# LCD-Shield_V2.net
KiCad netlist of a schematic drawn in EAGLE
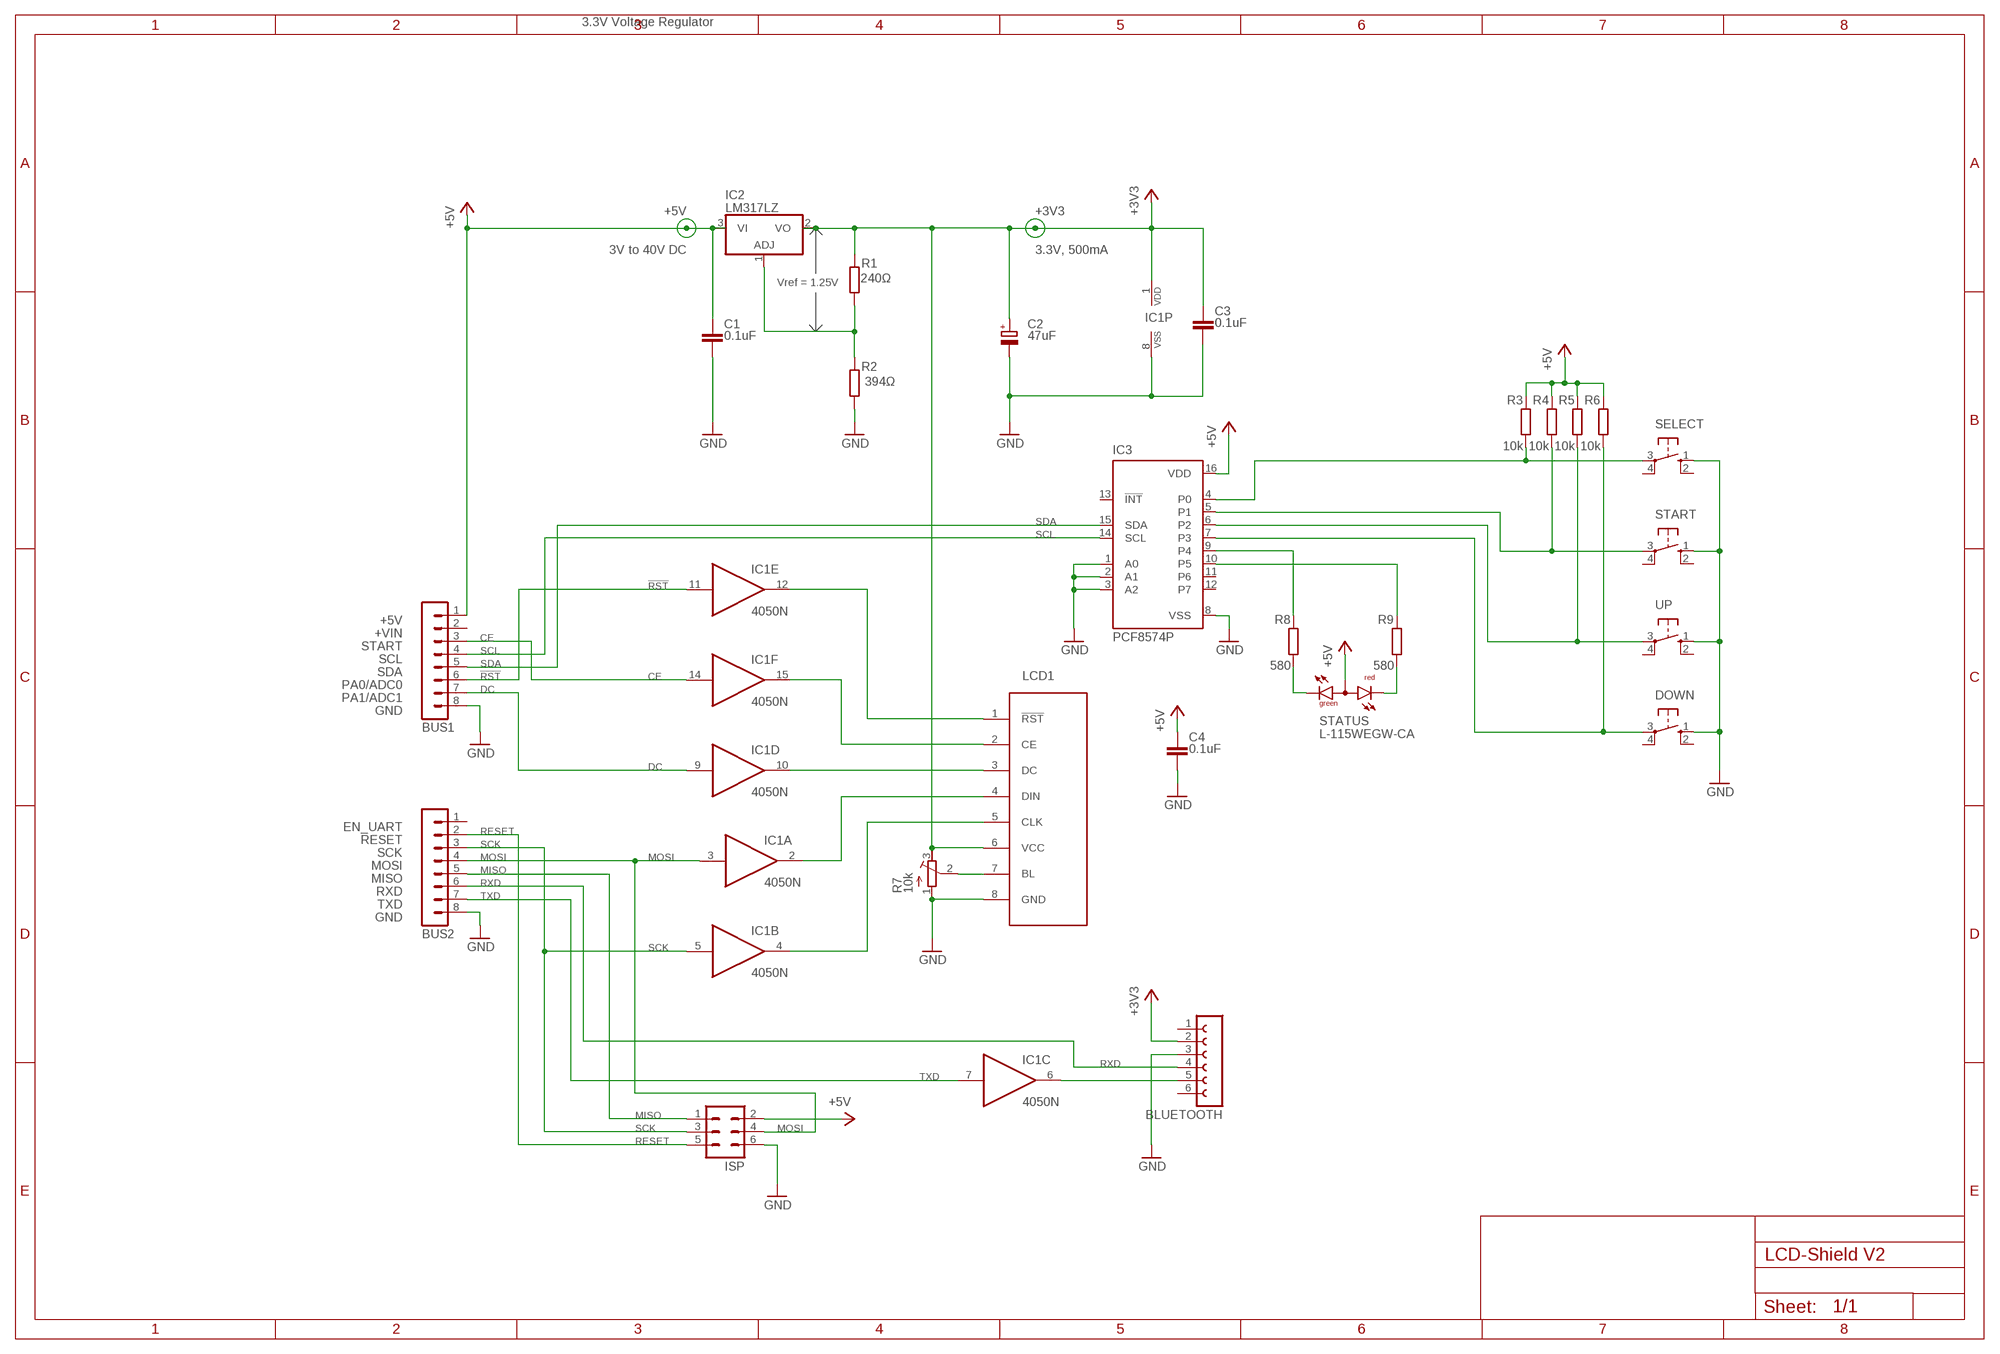
[diagram p0: schematic, sheet 1]

(export (version "E")
  (design (tool "Eeschema 10.0.6"))
  (components
    (comp (ref "BLUETOOTH")
      (value "FE06-1")
      (footprint "eagle-import:FE06")
      (libsource (lib "eagle-import") (part "FE06-1"))
    )
    (comp (ref "BUS1")
      (value "MA08-1")
      (footprint "eagle-import:MA08-1")
      (libsource (lib "eagle-import") (part "MA08-1"))
    )
    (comp (ref "BUS2")
      (value "MA08-1")
      (footprint "eagle-import:MA08-1")
      (libsource (lib "eagle-import") (part "MA08-1"))
    )
    (comp (ref "C1")
      (value "0.1uF")
      (footprint "eagle-import:C025-024X044")
      (libsource (lib "eagle-import") (part "C-EU025-024X044"))
    )
    (comp (ref "C2")
      (value "47uF")
      (footprint "eagle-import:E2-4")
      (libsource (lib "eagle-import") (part "CPOL-EUE2-4"))
    )
    (comp (ref "C3")
      (value "0.1uF")
      (footprint "eagle-import:C025-024X044")
      (libsource (lib "eagle-import") (part "C-EU025-024X044"))
    )
    (comp (ref "C4")
      (value "0.1uF")
      (footprint "eagle-import:C025-024X044")
      (libsource (lib "eagle-import") (part "C-EU025-024X044"))
    )
    (comp (ref "DOWN")
      (value "10-XX")
      (footprint "eagle-import:B3F-10XX")
      (fields (field (name "MPN") "B3F-1000"))
      (libsource (lib "eagle-import") (part "10-XX"))
    )
    (comp (ref "IC1")
      (value "4050N")
      (footprint "eagle-import:DIL16")
      (libsource (lib "eagle-import") (part "4050N"))
    )
    (comp (ref "IC2")
      (value "LM317LZ")
      (footprint "eagle-import:TO92")
      (libsource (lib "eagle-import") (part "317LZLM"))
    )
    (comp (ref "IC3")
      (value "PCF8574P")
      (footprint "eagle-import:DIL16")
      (fields (field (name "MPN") "PCF8574PN"))
      (libsource (lib "eagle-import") (part "PCF8574P"))
    )
    (comp (ref "ISP")
      (value "MA03-2")
      (footprint "eagle-import:MA03-2")
      (libsource (lib "eagle-import") (part "MA03-2"))
    )
    (comp (ref "LCD1")
      (value "5110_LCD_NOKIA")
      (footprint "eagle-import:LCD_5110")
      (libsource (lib "eagle-import") (part "5110_LCD_NOKIA"))
    )
    (comp (ref "R1")
      (value "240Ω")
      (footprint "eagle-import:0207_7")
      (libsource (lib "eagle-import") (part "R-EU_0207/7"))
    )
    (comp (ref "R2")
      (value "394Ω")
      (footprint "eagle-import:0207_7")
      (libsource (lib "eagle-import") (part "R-EU_0207/7"))
    )
    (comp (ref "R3")
      (value "10k")
      (footprint "eagle-import:0207_7")
      (libsource (lib "eagle-import") (part "R-EU_0207/7"))
    )
    (comp (ref "R4")
      (value "10k")
      (footprint "eagle-import:0207_7")
      (libsource (lib "eagle-import") (part "R-EU_0207/7"))
    )
    (comp (ref "R5")
      (value "10k")
      (footprint "eagle-import:0207_7")
      (libsource (lib "eagle-import") (part "R-EU_0207/7"))
    )
    (comp (ref "R6")
      (value "10k")
      (footprint "eagle-import:0207_7")
      (libsource (lib "eagle-import") (part "R-EU_0207/7"))
    )
    (comp (ref "R7")
      (value "10k")
      (footprint "eagle-import:RTRIM3296W")
      (libsource (lib "eagle-import") (part "R-TRIMM3296W"))
    )
    (comp (ref "R8")
      (value "580")
      (footprint "eagle-import:0207_7")
      (libsource (lib "eagle-import") (part "R-EU_0207/7"))
    )
    (comp (ref "R9")
      (value "580")
      (footprint "eagle-import:0207_7")
      (libsource (lib "eagle-import") (part "R-EU_0207/7"))
    )
    (comp (ref "SELECT")
      (value "10-XX")
      (footprint "eagle-import:B3F-10XX")
      (fields (field (name "MPN") "B3F-1000"))
      (libsource (lib "eagle-import") (part "10-XX"))
    )
    (comp (ref "START")
      (value "10-XX")
      (footprint "eagle-import:B3F-10XX")
      (fields (field (name "MPN") "B3F-1000"))
      (libsource (lib "eagle-import") (part "10-XX"))
    )
    (comp (ref "STATUS")
      (value "L-115WEGW-CA")
      (footprint "eagle-import:DUOLED-A-3MM")
      (libsource (lib "eagle-import") (part "L-115WEGW-CA"))
    )
    (comp (ref "UP")
      (value "10-XX")
      (footprint "eagle-import:B3F-10XX")
      (fields (field (name "MPN") "B3F-1000"))
      (libsource (lib "eagle-import") (part "10-XX"))
    )
  )
  (nets
    (net (code "1") (name "+3V3") (class "Default")
      (node (ref "BLUETOOTH") (pin "2") (pinfunction "2_2") (pintype "passive"))
      (node (ref "C2") (pin "+") (pinfunction "+_+") (pintype "passive"))
      (node (ref "C3") (pin "1") (pinfunction "1_1") (pintype "passive"))
      (node (ref "IC1") (pin "1") (pinfunction "VDD_1") (pintype "power_in"))
      (node (ref "IC2") (pin "2") (pinfunction "VO_2") (pintype "passive"))
      (node (ref "LCD1") (pin "6") (pinfunction "VCC_6") (pintype "bidirectional"))
      (node (ref "R1") (pin "2") (pinfunction "2_2") (pintype "passive"))
      (node (ref "R7") (pin "3") (pinfunction "E_3") (pintype "passive"))
    )
    (net (code "2") (name "+5V") (class "Default")
      (node (ref "BUS1") (pin "1") (pinfunction "1_1") (pintype "passive"))
      (node (ref "C1") (pin "1") (pinfunction "1_1") (pintype "passive"))
      (node (ref "C4") (pin "1") (pinfunction "1_1") (pintype "passive"))
      (node (ref "IC2") (pin "3") (pinfunction "VI_3") (pintype "input"))
      (node (ref "IC3") (pin "16") (pinfunction "VDD_16") (pintype "power_in"))
      (node (ref "ISP") (pin "2") (pinfunction "2_2") (pintype "passive"))
      (node (ref "R3") (pin "2") (pinfunction "2_2") (pintype "passive"))
      (node (ref "R4") (pin "2") (pinfunction "2_2") (pintype "passive"))
      (node (ref "R5") (pin "2") (pinfunction "2_2") (pintype "passive"))
      (node (ref "R6") (pin "2") (pinfunction "2_2") (pintype "passive"))
      (node (ref "STATUS") (pin "2") (pinfunction "A_2") (pintype "passive"))
    )
    (net (code "3") (name "/CE") (class "Default")
      (node (ref "BUS1") (pin "3") (pinfunction "3_3") (pintype "passive"))
      (node (ref "IC1") (pin "14") (pinfunction "I_14") (pintype "input"))
    )
    (net (code "4") (name "/DC") (class "Default")
      (node (ref "BUS1") (pin "7") (pinfunction "7_7") (pintype "passive"))
      (node (ref "IC1") (pin "9") (pinfunction "I_9") (pintype "input"))
    )
    (net (code "5") (name "/MISO") (class "Default")
      (node (ref "BUS2") (pin "5") (pinfunction "5_5") (pintype "passive"))
      (node (ref "ISP") (pin "1") (pinfunction "1_1") (pintype "passive"))
    )
    (net (code "6") (name "/MOSI") (class "Default")
      (node (ref "BUS2") (pin "4") (pinfunction "4_4") (pintype "passive"))
      (node (ref "IC1") (pin "3") (pinfunction "I_3") (pintype "input"))
      (node (ref "ISP") (pin "4") (pinfunction "4_4") (pintype "passive"))
    )
    (net (code "7") (name "/RESET") (class "Default")
      (node (ref "BUS2") (pin "2") (pinfunction "2_2") (pintype "passive"))
      (node (ref "ISP") (pin "5") (pinfunction "5_5") (pintype "passive"))
    )
    (net (code "8") (name "/RXD") (class "Default")
      (node (ref "BLUETOOTH") (pin "4") (pinfunction "4_4") (pintype "passive"))
      (node (ref "BUS2") (pin "6") (pinfunction "6_6") (pintype "passive"))
    )
    (net (code "9") (name "/SCK") (class "Default")
      (node (ref "BUS2") (pin "3") (pinfunction "3_3") (pintype "passive"))
      (node (ref "IC1") (pin "5") (pinfunction "I_5") (pintype "input"))
      (node (ref "ISP") (pin "3") (pinfunction "3_3") (pintype "passive"))
    )
    (net (code "10") (name "/SCL") (class "Default")
      (node (ref "BUS1") (pin "4") (pinfunction "4_4") (pintype "passive"))
      (node (ref "IC3") (pin "14") (pinfunction "SCL_14") (pintype "input"))
    )
    (net (code "11") (name "/SDA") (class "Default")
      (node (ref "BUS1") (pin "5") (pinfunction "5_5") (pintype "passive"))
      (node (ref "IC3") (pin "15") (pinfunction "SDA_15") (pintype "bidirectional"))
    )
    (net (code "12") (name "/TXD") (class "Default")
      (node (ref "BUS2") (pin "7") (pinfunction "7_7") (pintype "passive"))
      (node (ref "IC1") (pin "7") (pinfunction "I_7") (pintype "input"))
    )
    (net (code "13") (name "/~{RST}") (class "Default")
      (node (ref "BUS1") (pin "6") (pinfunction "6_6") (pintype "passive"))
      (node (ref "IC1") (pin "11") (pinfunction "I_11") (pintype "input"))
    )
    (net (code "14") (name "GND") (class "Default")
      (node (ref "BLUETOOTH") (pin "3") (pinfunction "3_3") (pintype "passive"))
      (node (ref "BUS1") (pin "8") (pinfunction "8_8") (pintype "passive"))
      (node (ref "BUS2") (pin "8") (pinfunction "8_8") (pintype "passive"))
      (node (ref "C1") (pin "2") (pinfunction "2_2") (pintype "passive"))
      (node (ref "C2") (pin "-") (pinfunction "-_-") (pintype "passive"))
      (node (ref "C3") (pin "2") (pinfunction "2_2") (pintype "passive"))
      (node (ref "C4") (pin "2") (pinfunction "2_2") (pintype "passive"))
      (node (ref "DOWN") (pin "1") (pinfunction "S_1") (pintype "passive"))
      (node (ref "IC1") (pin "8") (pinfunction "VSS_8") (pintype "power_in"))
      (node (ref "IC3") (pin "1") (pinfunction "A0_1") (pintype "input"))
      (node (ref "IC3") (pin "2") (pinfunction "A1_2") (pintype "input"))
      (node (ref "IC3") (pin "3") (pinfunction "A2_3") (pintype "input"))
      (node (ref "IC3") (pin "8") (pinfunction "VSS_8") (pintype "power_in"))
      (node (ref "ISP") (pin "6") (pinfunction "6_6") (pintype "passive"))
      (node (ref "LCD1") (pin "8") (pinfunction "GND_8") (pintype "bidirectional"))
      (node (ref "R2") (pin "1") (pinfunction "1_1") (pintype "passive"))
      (node (ref "R7") (pin "1") (pinfunction "A_1") (pintype "passive"))
      (node (ref "SELECT") (pin "1") (pinfunction "S_1") (pintype "passive"))
      (node (ref "START") (pin "1") (pinfunction "S_1") (pintype "passive"))
      (node (ref "UP") (pin "1") (pinfunction "S_1") (pintype "passive"))
    )
    (net (code "15") (name "Net-(DOWN-P)") (class "Default")
      (node (ref "DOWN") (pin "3") (pinfunction "P_3") (pintype "passive"))
      (node (ref "IC3") (pin "7") (pinfunction "P3_7") (pintype "bidirectional"))
      (node (ref "R6") (pin "1") (pinfunction "1_1") (pintype "passive"))
    )
    (net (code "16") (name "Net-(IC1A-O)") (class "Default")
      (node (ref "IC1") (pin "2") (pinfunction "O_2") (pintype "output"))
      (node (ref "LCD1") (pin "4") (pinfunction "DIN_4") (pintype "bidirectional"))
    )
    (net (code "17") (name "Net-(IC1B-O)") (class "Default")
      (node (ref "IC1") (pin "4") (pinfunction "O_4") (pintype "output"))
      (node (ref "LCD1") (pin "5") (pinfunction "CLK_5") (pintype "bidirectional"))
    )
    (net (code "18") (name "Net-(IC1C-O)") (class "Default")
      (node (ref "BLUETOOTH") (pin "5") (pinfunction "5_5") (pintype "passive"))
      (node (ref "IC1") (pin "6") (pinfunction "O_6") (pintype "output"))
    )
    (net (code "19") (name "Net-(IC1D-O)") (class "Default")
      (node (ref "IC1") (pin "10") (pinfunction "O_10") (pintype "output"))
      (node (ref "LCD1") (pin "3") (pinfunction "DC_3") (pintype "bidirectional"))
    )
    (net (code "20") (name "Net-(IC1E-O)") (class "Default")
      (node (ref "IC1") (pin "12") (pinfunction "O_12") (pintype "output"))
      (node (ref "LCD1") (pin "1") (pinfunction "~{RST}_1") (pintype "bidirectional"))
    )
    (net (code "21") (name "Net-(IC1F-O)") (class "Default")
      (node (ref "IC1") (pin "15") (pinfunction "O_15") (pintype "output"))
      (node (ref "LCD1") (pin "2") (pinfunction "CE_2") (pintype "bidirectional"))
    )
    (net (code "22") (name "Net-(IC2-ADJ)") (class "Default")
      (node (ref "IC2") (pin "1") (pinfunction "ADJ_1") (pintype "input"))
      (node (ref "R1") (pin "1") (pinfunction "1_1") (pintype "passive"))
      (node (ref "R2") (pin "2") (pinfunction "2_2") (pintype "passive"))
    )
    (net (code "23") (name "Net-(IC3-P0)") (class "Default")
      (node (ref "IC3") (pin "4") (pinfunction "P0_4") (pintype "bidirectional"))
      (node (ref "R3") (pin "1") (pinfunction "1_1") (pintype "passive"))
      (node (ref "SELECT") (pin "3") (pinfunction "P_3") (pintype "passive"))
    )
    (net (code "24") (name "Net-(IC3-P1)") (class "Default")
      (node (ref "IC3") (pin "5") (pinfunction "P1_5") (pintype "bidirectional"))
      (node (ref "R4") (pin "1") (pinfunction "1_1") (pintype "passive"))
      (node (ref "START") (pin "3") (pinfunction "P_3") (pintype "passive"))
    )
    (net (code "25") (name "Net-(IC3-P2)") (class "Default")
      (node (ref "IC3") (pin "6") (pinfunction "P2_6") (pintype "bidirectional"))
      (node (ref "R5") (pin "1") (pinfunction "1_1") (pintype "passive"))
      (node (ref "UP") (pin "3") (pinfunction "P_3") (pintype "passive"))
    )
    (net (code "26") (name "Net-(IC3-P4)") (class "Default")
      (node (ref "IC3") (pin "9") (pinfunction "P4_9") (pintype "bidirectional"))
      (node (ref "R8") (pin "2") (pinfunction "2_2") (pintype "passive"))
    )
    (net (code "27") (name "Net-(IC3-P5)") (class "Default")
      (node (ref "IC3") (pin "10") (pinfunction "P5_10") (pintype "bidirectional"))
      (node (ref "R9") (pin "2") (pinfunction "2_2") (pintype "passive"))
    )
    (net (code "28") (name "Net-(LCD1-BL)") (class "Default")
      (node (ref "LCD1") (pin "7") (pinfunction "BL_7") (pintype "bidirectional"))
      (node (ref "R7") (pin "2") (pinfunction "S_2") (pintype "passive"))
    )
    (net (code "29") (name "Net-(STATUS-CG)") (class "Default")
      (node (ref "R8") (pin "1") (pinfunction "1_1") (pintype "passive"))
      (node (ref "STATUS") (pin "1") (pinfunction "CG_1") (pintype "passive"))
    )
    (net (code "30") (name "Net-(STATUS-CR)") (class "Default")
      (node (ref "R9") (pin "1") (pinfunction "1_1") (pintype "passive"))
      (node (ref "STATUS") (pin "3") (pinfunction "CR_3") (pintype "passive"))
    )
    (net (code "31") (name "unconnected-(BLUETOOTH-Pad1)") (class "Default")
      (node (ref "BLUETOOTH") (pin "1") (pinfunction "1_1") (pintype "passive"))
    )
    (net (code "32") (name "unconnected-(BLUETOOTH-Pad6)") (class "Default")
      (node (ref "BLUETOOTH") (pin "6") (pinfunction "6_6") (pintype "passive"))
    )
    (net (code "33") (name "unconnected-(BUS1-Pad2)") (class "Default")
      (node (ref "BUS1") (pin "2") (pinfunction "2_2") (pintype "passive"))
    )
    (net (code "34") (name "unconnected-(BUS2-Pad1)") (class "Default")
      (node (ref "BUS2") (pin "1") (pinfunction "1_1") (pintype "passive"))
    )
    (net (code "35") (name "unconnected-(DOWN-P1-Pad4)") (class "Default")
      (node (ref "DOWN") (pin "4") (pinfunction "P1_4") (pintype "passive"))
    )
    (net (code "36") (name "unconnected-(DOWN-S1-Pad2)") (class "Default")
      (node (ref "DOWN") (pin "2") (pinfunction "S1_2") (pintype "passive"))
    )
    (net (code "37") (name "unconnected-(IC3-P6-Pad11)") (class "Default")
      (node (ref "IC3") (pin "11") (pinfunction "P6_11") (pintype "bidirectional"))
    )
    (net (code "38") (name "unconnected-(IC3-P7-Pad12)") (class "Default")
      (node (ref "IC3") (pin "12") (pinfunction "P7_12") (pintype "bidirectional"))
    )
    (net (code "39") (name "unconnected-(IC3-~{INT}-Pad13)") (class "Default")
      (node (ref "IC3") (pin "13") (pinfunction "~{INT}_13") (pintype "output"))
    )
    (net (code "40") (name "unconnected-(SELECT-P1-Pad4)") (class "Default")
      (node (ref "SELECT") (pin "4") (pinfunction "P1_4") (pintype "passive"))
    )
    (net (code "41") (name "unconnected-(SELECT-S1-Pad2)") (class "Default")
      (node (ref "SELECT") (pin "2") (pinfunction "S1_2") (pintype "passive"))
    )
    (net (code "42") (name "unconnected-(START-P1-Pad4)") (class "Default")
      (node (ref "START") (pin "4") (pinfunction "P1_4") (pintype "passive"))
    )
    (net (code "43") (name "unconnected-(START-S1-Pad2)") (class "Default")
      (node (ref "START") (pin "2") (pinfunction "S1_2") (pintype "passive"))
    )
    (net (code "44") (name "unconnected-(UP-P1-Pad4)") (class "Default")
      (node (ref "UP") (pin "4") (pinfunction "P1_4") (pintype "passive"))
    )
    (net (code "45") (name "unconnected-(UP-S1-Pad2)") (class "Default")
      (node (ref "UP") (pin "2") (pinfunction "S1_2") (pintype "passive"))
    )
  )
)
